# CPLD.net
KiCad netlist of a schematic drawn in Altium Designer
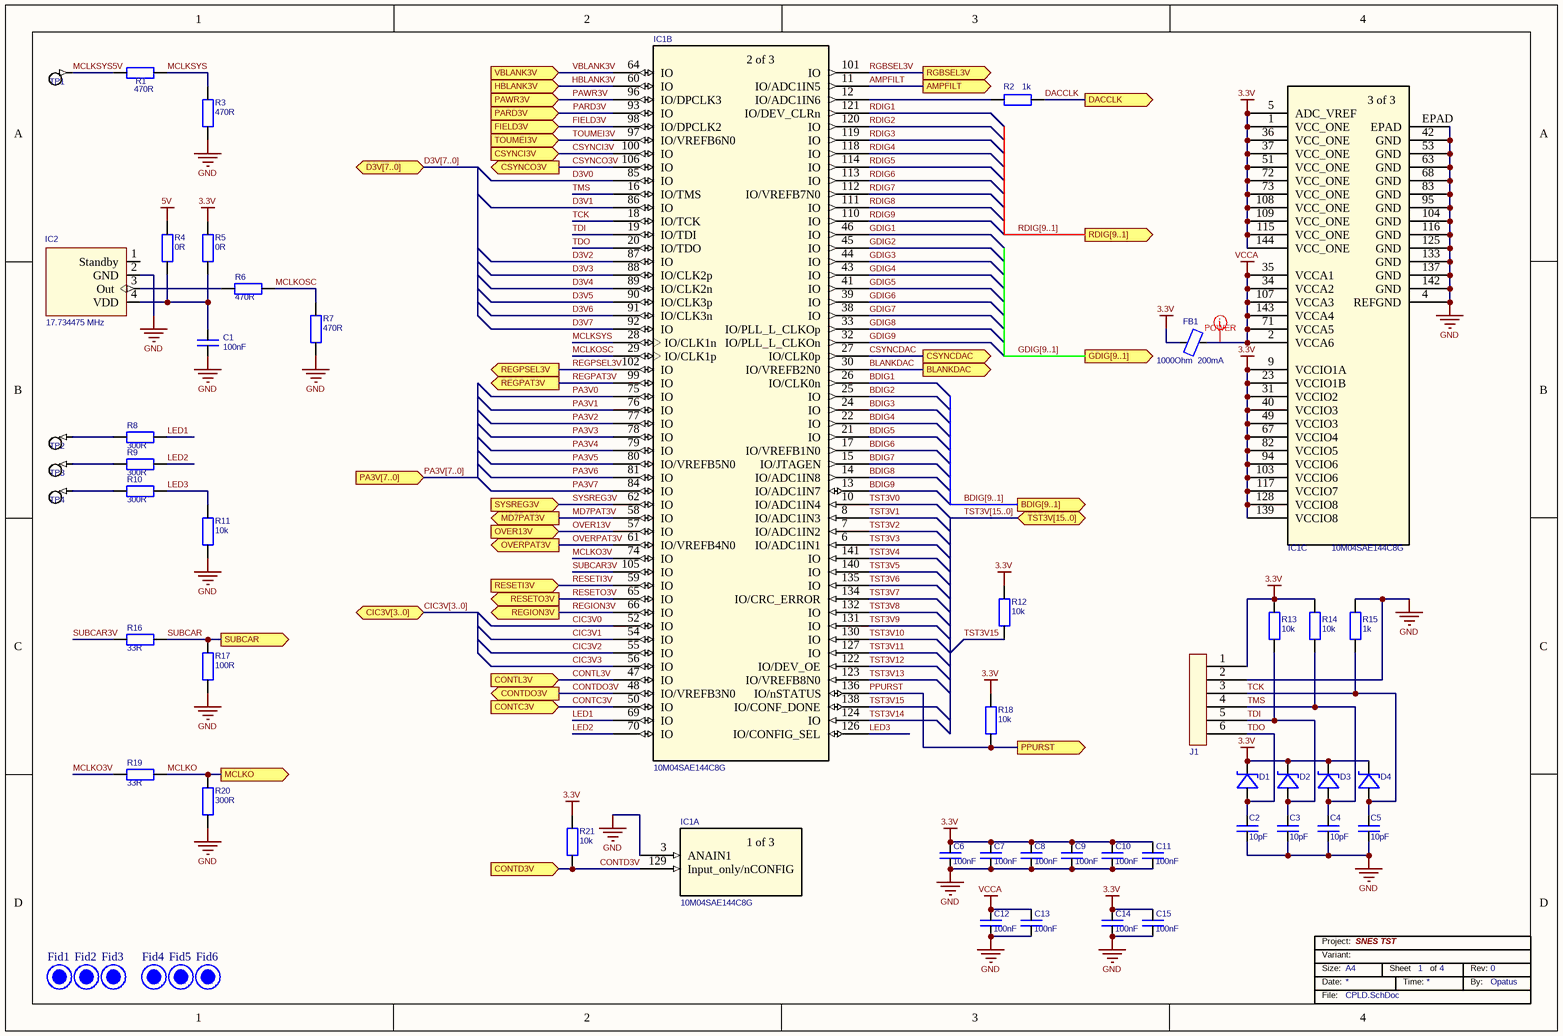
[diagram p0: CPLD.SchDoc]

(export (version "E")
  (design (tool "Eeschema 10.0.6"))
  (components
    (comp (ref "C1")
      (value "100nF")
      (footprint "Cap_0402_Chip")
      (fields
        (field (name "TOLERANCE") "±20%")
        (field (name "Comment") "Ceramic Capacitor 100nF 10V ±20% X7R 0402")
      )
      (libsource (lib "PCB") (part "Capacitor"))
    )
    (comp (ref "C2")
      (value "10pF")
      (footprint "Cap_0402_Chip")
      (fields
        (field (name "TOLERANCE") "±20%")
        (field (name "Comment") "Ceramic Capacitor 10pF 10V ±20% X7R 0402")
      )
      (libsource (lib "PCB") (part "Capacitor"))
    )
    (comp (ref "C3")
      (value "10pF")
      (footprint "Cap_0402_Chip")
      (fields
        (field (name "TOLERANCE") "±20%")
        (field (name "Comment") "Ceramic Capacitor 10pF 10V ±20% X7R 0402")
      )
      (libsource (lib "PCB") (part "Capacitor"))
    )
    (comp (ref "C4")
      (value "10pF")
      (footprint "Cap_0402_Chip")
      (fields
        (field (name "TOLERANCE") "±20%")
        (field (name "Comment") "Ceramic Capacitor 10pF 10V ±20% X7R 0402")
      )
      (libsource (lib "PCB") (part "Capacitor"))
    )
    (comp (ref "C5")
      (value "10pF")
      (footprint "Cap_0402_Chip")
      (fields
        (field (name "TOLERANCE") "±20%")
        (field (name "Comment") "Ceramic Capacitor 10pF 10V ±20% X7R 0402")
      )
      (libsource (lib "PCB") (part "Capacitor"))
    )
    (comp (ref "C6")
      (value "100nF")
      (footprint "Cap_0402_Chip")
      (fields
        (field (name "TOLERANCE") "±20%")
        (field (name "Comment") "Ceramic Capacitor 100nF 10V ±20% X7R 0402")
      )
      (libsource (lib "PCB") (part "Capacitor"))
    )
    (comp (ref "C7")
      (value "100nF")
      (footprint "Cap_0402_Chip")
      (fields
        (field (name "TOLERANCE") "±20%")
        (field (name "Comment") "Ceramic Capacitor 100nF 10V ±20% X7R 0402")
      )
      (libsource (lib "PCB") (part "Capacitor"))
    )
    (comp (ref "C8")
      (value "100nF")
      (footprint "Cap_0402_Chip")
      (fields
        (field (name "TOLERANCE") "±20%")
        (field (name "Comment") "Ceramic Capacitor 100nF 10V ±20% X7R 0402")
      )
      (libsource (lib "PCB") (part "Capacitor"))
    )
    (comp (ref "C9")
      (value "100nF")
      (footprint "Cap_0402_Chip")
      (fields
        (field (name "TOLERANCE") "±20%")
        (field (name "Comment") "Ceramic Capacitor 100nF 10V ±20% X7R 0402")
      )
      (libsource (lib "PCB") (part "Capacitor"))
    )
    (comp (ref "C10")
      (value "100nF")
      (footprint "Cap_0402_Chip")
      (fields
        (field (name "TOLERANCE") "±20%")
        (field (name "Comment") "Ceramic Capacitor 100nF 10V ±20% X7R 0402")
      )
      (libsource (lib "PCB") (part "Capacitor"))
    )
    (comp (ref "C11")
      (value "100nF")
      (footprint "Cap_0402_Chip")
      (fields
        (field (name "TOLERANCE") "±20%")
        (field (name "Comment") "Ceramic Capacitor 100nF 10V ±20% X7R 0402")
      )
      (libsource (lib "PCB") (part "Capacitor"))
    )
    (comp (ref "C12")
      (value "100nF")
      (footprint "Cap_0402_Chip")
      (fields
        (field (name "TOLERANCE") "±20%")
        (field (name "Comment") "Ceramic Capacitor 100nF 10V ±20% X7R 0402")
      )
      (libsource (lib "PCB") (part "Capacitor"))
    )
    (comp (ref "C13")
      (value "100nF")
      (footprint "Cap_0402_Chip")
      (fields
        (field (name "TOLERANCE") "±20%")
        (field (name "Comment") "Ceramic Capacitor 100nF 10V ±20% X7R 0402")
      )
      (libsource (lib "PCB") (part "Capacitor"))
    )
    (comp (ref "C14")
      (value "100nF")
      (footprint "Cap_0402_Chip")
      (fields
        (field (name "TOLERANCE") "±20%")
        (field (name "Comment") "Ceramic Capacitor 100nF 10V ±20% X7R 0402")
      )
      (libsource (lib "PCB") (part "Capacitor"))
    )
    (comp (ref "C15")
      (value "100nF")
      (footprint "Cap_0402_Chip")
      (fields
        (field (name "TOLERANCE") "±20%")
        (field (name "Comment") "Ceramic Capacitor 100nF 10V ±20% X7R 0402")
      )
      (libsource (lib "PCB") (part "Capacitor"))
    )
    (comp (ref "D1")
      (value "BAT54WS")
      (footprint "SOD323")
      (description "Schottky Diode")
      (fields (field (name "MANUFACTURER_PART_NUMBER") "BAT54WS-7-F"))
      (libsource (lib "PCB") (part "Schottky Diode"))
    )
    (comp (ref "D2")
      (value "BAT54WS")
      (footprint "SOD323")
      (description "Schottky Diode")
      (fields (field (name "MANUFACTURER_PART_NUMBER") "BAT54WS-7-F"))
      (libsource (lib "PCB") (part "Schottky Diode"))
    )
    (comp (ref "D3")
      (value "BAT54WS")
      (footprint "SOD323")
      (description "Schottky Diode")
      (fields (field (name "MANUFACTURER_PART_NUMBER") "BAT54WS-7-F"))
      (libsource (lib "PCB") (part "Schottky Diode"))
    )
    (comp (ref "D4")
      (value "BAT54WS")
      (footprint "SOD323")
      (description "Schottky Diode")
      (fields (field (name "MANUFACTURER_PART_NUMBER") "BAT54WS-7-F"))
      (libsource (lib "PCB") (part "Schottky Diode"))
    )
    (comp (ref "FB1")
      (value "1000Ohm  200mA")
      (footprint "Ind_0402_Chip")
      (fields (field (name "MANUFACTURER_PART_NUMBER") "MMZ1005S102CT000"))
      (libsource (lib "PCB") (part "Ferrite Bead"))
    )
    (comp (ref "Fid1")
      (value "Fiducial")
      (footprint "Fiducial_1_side")
      (libsource (lib "PCB") (part "Fiducial"))
    )
    (comp (ref "Fid2")
      (value "Fiducial")
      (footprint "Fiducial_1_side")
      (libsource (lib "PCB") (part "Fiducial"))
    )
    (comp (ref "Fid3")
      (value "Fiducial")
      (footprint "Fiducial_1_side")
      (libsource (lib "PCB") (part "Fiducial"))
    )
    (comp (ref "Fid4")
      (value "Fiducial")
      (footprint "Fiducial_1_side")
      (libsource (lib "PCB") (part "Fiducial"))
    )
    (comp (ref "Fid5")
      (value "Fiducial")
      (footprint "Fiducial_1_side")
      (libsource (lib "PCB") (part "Fiducial"))
    )
    (comp (ref "Fid6")
      (value "Fiducial")
      (footprint "Fiducial_1_side")
      (libsource (lib "PCB") (part "Fiducial"))
    )
    (comp (ref "IC1")
      (value "10M04SAE144C8G")
      (footprint "EQFP-144_A:1P65_")
      (description "No Description Available")
      (fields (field (name "COPYRIGHT") "Copyright (C) 2018 Accelerated Designs. All rights reserved"))
      (libsource (lib "") (part "10M08SAE144C8G_1"))
    )
    (comp (ref "IC2")
      (value "17.734475 MHz")
      (footprint "Quarz 7.5mm")
      (description "Oscillator")
      (fields
        (field (name "FREQUENCY") "17.734475 MHz")
        (field (name "MANUFACTURER_PART_NUMBER") "LFSPXO020648Bulk")
      )
      (libsource (lib "PCB") (part "Oscillator"))
    )
    (comp (ref "J1")
      (value "Conn 6P")
      (footprint "Con6P")
      (description "6 Pole Connector")
      (libsource (lib "PCB") (part "Conn 6P"))
    )
    (comp (ref "R1")
      (value "470R")
      (footprint "Res_0603_Chip")
      (fields (field (name "TOLERANCE") "±1%") (field (name "Comment") "Resistor 470R 0603 ±1%"))
      (libsource (lib "") (part "R_1"))
    )
    (comp (ref "R2")
      (value "1k")
      (footprint "Res_0402_Chip")
      (fields (field (name "TOLERANCE") "±1%") (field (name "Comment") "Resistor 1k 0402 ±1%"))
      (libsource (lib "") (part "R_2"))
    )
    (comp (ref "R3")
      (value "470R")
      (footprint "Res_0603_Chip")
      (fields (field (name "TOLERANCE") "±1%") (field (name "Comment") "Resistor 470R 0603 ±1%"))
      (libsource (lib "PCB") (part "R"))
    )
    (comp (ref "R4")
      (value "0R")
      (footprint "Res_0402_Chip")
      (fields (field (name "Comment") "Resistor 0R 0402 "))
      (libsource (lib "PCB") (part "R"))
    )
    (comp (ref "R5")
      (value "0R")
      (footprint "Res_0402_Chip")
      (fields (field (name "Comment") "Resistor 0R 0402 "))
      (libsource (lib "PCB") (part "R"))
    )
    (comp (ref "R6")
      (value "470R")
      (footprint "Res_0603_Chip")
      (fields (field (name "TOLERANCE") "±1%") (field (name "Comment") "Resistor 470R 0603 ±1%"))
      (libsource (lib "") (part "R_1"))
    )
    (comp (ref "R7")
      (value "470R")
      (footprint "Res_0603_Chip")
      (fields (field (name "TOLERANCE") "±1%") (field (name "Comment") "Resistor 470R 0603 ±1%"))
      (libsource (lib "PCB") (part "R"))
    )
    (comp (ref "R8")
      (value "300R")
      (footprint "Res_0603_Chip")
      (fields (field (name "TOLERANCE") "±1%") (field (name "Comment") "Resistor 300R 0603 ±1%"))
      (libsource (lib "") (part "R_2"))
    )
    (comp (ref "R9")
      (value "300R")
      (footprint "Res_0603_Chip")
      (fields (field (name "TOLERANCE") "±1%") (field (name "Comment") "Resistor 300R 0603 ±1%"))
      (libsource (lib "") (part "R_2"))
    )
    (comp (ref "R10")
      (value "300R")
      (footprint "Res_0603_Chip")
      (fields (field (name "TOLERANCE") "±1%") (field (name "Comment") "Resistor 300R 0603 ±1%"))
      (libsource (lib "") (part "R_2"))
    )
    (comp (ref "R11")
      (value "10k")
      (footprint "Res_0402_Chip")
      (fields (field (name "TOLERANCE") "±1%") (field (name "Comment") "Resistor 10k 0402 ±1%"))
      (libsource (lib "") (part "R_3"))
    )
    (comp (ref "R12")
      (value "10k")
      (footprint "Res_0402_Chip")
      (fields (field (name "TOLERANCE") "±1%") (field (name "Comment") "Resistor 10k 0402 ±1%"))
      (libsource (lib "PCB") (part "R"))
    )
    (comp (ref "R13")
      (value "10k")
      (footprint "Res_0402_Chip")
      (fields (field (name "TOLERANCE") "±1%") (field (name "Comment") "Resistor 10k 0402 ±1%"))
      (libsource (lib "PCB") (part "R"))
    )
    (comp (ref "R14")
      (value "10k")
      (footprint "Res_0402_Chip")
      (fields (field (name "TOLERANCE") "±1%") (field (name "Comment") "Resistor 10k 0402 ±1%"))
      (libsource (lib "PCB") (part "R"))
    )
    (comp (ref "R15")
      (value "1k")
      (footprint "Res_0402_Chip")
      (fields (field (name "TOLERANCE") "±1%") (field (name "Comment") "Resistor 1k 0402 ±1%"))
      (libsource (lib "") (part "R_3"))
    )
    (comp (ref "R16")
      (value "33R")
      (footprint "Res_0603_Chip")
      (fields (field (name "TOLERANCE") "±1%") (field (name "Comment") "Resistor 33R 0603 ±1%"))
      (libsource (lib "") (part "R_1"))
    )
    (comp (ref "R17")
      (value "100R")
      (footprint "Res_0603_Chip")
      (fields (field (name "TOLERANCE") "±1%") (field (name "Comment") "Resistor 100R 0603 ±1%"))
      (libsource (lib "PCB") (part "R"))
    )
    (comp (ref "R18")
      (value "10k")
      (footprint "Res_0402_Chip")
      (fields (field (name "TOLERANCE") "±1%") (field (name "Comment") "Resistor 10k 0402 ±1%"))
      (libsource (lib "PCB") (part "R"))
    )
    (comp (ref "R19")
      (value "33R")
      (footprint "Res_0603_Chip")
      (fields (field (name "TOLERANCE") "±1%") (field (name "Comment") "Resistor 33R 0603 ±1%"))
      (libsource (lib "") (part "R_1"))
    )
    (comp (ref "R20")
      (value "300R")
      (footprint "Res_0603_Chip")
      (fields (field (name "TOLERANCE") "±1%") (field (name "Comment") "Resistor 300R 0603 ±1%"))
      (libsource (lib "PCB") (part "R"))
    )
    (comp (ref "R21")
      (value "10k")
      (footprint "Res_0402_Chip")
      (fields (field (name "TOLERANCE") "±1%") (field (name "Comment") "Resistor 10k 0402 ±1%"))
      (libsource (lib "PCB") (part "R"))
    )
    (comp (ref "TP1")
      (value "Pin Connector")
      (footprint "Pin Connector Small")
      (libsource (lib "PCB") (part "Pin Connector"))
    )
    (comp (ref "TP2")
      (value "Pin Connector")
      (footprint "Pin Connector Small")
      (libsource (lib "PCB") (part "Pin Connector"))
    )
    (comp (ref "TP3")
      (value "Pin Connector")
      (footprint "Pin Connector Small")
      (libsource (lib "PCB") (part "Pin Connector"))
    )
    (comp (ref "TP4")
      (value "Pin Connector")
      (footprint "Pin Connector Small")
      (libsource (lib "PCB") (part "Pin Connector"))
    )
  )
  (nets
    (net (code "1") (name "/AMPFILT") (class "Default")
      (node (ref "IC1") (pin "11") (pinfunction "IO/ADC1IN5_11") (pintype "output"))
    )
    (net (code "2") (name "/BDIG1") (class "Default")
      (node (ref "IC1") (pin "26") (pinfunction "IO/CLK0n_26") (pintype "output"))
    )
    (net (code "3") (name "/BDIG2") (class "Default")
      (node (ref "IC1") (pin "25") (pinfunction "IO_25") (pintype "output"))
    )
    (net (code "4") (name "/BDIG3") (class "Default")
      (node (ref "IC1") (pin "24") (pinfunction "IO_24") (pintype "output"))
    )
    (net (code "5") (name "/BDIG4") (class "Default")
      (node (ref "IC1") (pin "22") (pinfunction "IO_22") (pintype "output"))
    )
    (net (code "6") (name "/BDIG5") (class "Default")
      (node (ref "IC1") (pin "21") (pinfunction "IO_21") (pintype "output"))
    )
    (net (code "7") (name "/BDIG6") (class "Default")
      (node (ref "IC1") (pin "17") (pinfunction "IO/VREFB1N0_17") (pintype "output"))
    )
    (net (code "8") (name "/BDIG7") (class "Default")
      (node (ref "IC1") (pin "15") (pinfunction "IO/JTAGEN_15") (pintype "output"))
    )
    (net (code "9") (name "/BDIG8") (class "Default")
      (node (ref "IC1") (pin "14") (pinfunction "IO/ADC1IN8_14") (pintype "output"))
    )
    (net (code "10") (name "/BDIG9") (class "Default")
      (node (ref "IC1") (pin "13") (pinfunction "IO/ADC1IN7_13") (pintype "bidirectional"))
    )
    (net (code "12") (name "/BLANKDAC") (class "Default")
      (node (ref "IC1") (pin "30") (pinfunction "IO/VREFB2N0_30") (pintype "output"))
    )
    (net (code "13") (name "/CIC3V0") (class "Default")
      (node (ref "IC1") (pin "52") (pinfunction "IO_52") (pintype "bidirectional"))
    )
    (net (code "14") (name "/CIC3V1") (class "Default")
      (node (ref "IC1") (pin "54") (pinfunction "IO_54") (pintype "bidirectional"))
    )
    (net (code "15") (name "/CIC3V2") (class "Default")
      (node (ref "IC1") (pin "55") (pinfunction "IO_55") (pintype "bidirectional"))
    )
    (net (code "16") (name "/CIC3V3") (class "Default")
      (node (ref "IC1") (pin "56") (pinfunction "IO_56") (pintype "bidirectional"))
    )
    (net (code "18") (name "/CONTC3V") (class "Default")
      (node (ref "IC1") (pin "50") (pinfunction "IO_50") (pintype "bidirectional"))
    )
    (net (code "19") (name "/CONTD3V") (class "Default")
      (node (ref "IC1") (pin "129") (pinfunction "Input_only/nCONFIG_129") (pintype "input"))
      (node (ref "R21") (pin "2") (pintype "passive"))
    )
    (net (code "20") (name "/CONTDO3V") (class "Default")
      (node (ref "IC1") (pin "48") (pinfunction "IO/VREFB3N0_48") (pintype "bidirectional"))
    )
    (net (code "21") (name "/CONTL3V") (class "Default")
      (node (ref "IC1") (pin "47") (pinfunction "IO_47") (pintype "bidirectional"))
    )
    (net (code "22") (name "/CSYNCDAC") (class "Default")
      (node (ref "IC1") (pin "27") (pinfunction "IO/CLK0p_27") (pintype "output"))
    )
    (net (code "23") (name "/CSYNCI3V") (class "Default")
      (node (ref "IC1") (pin "100") (pinfunction "IO_100") (pintype "bidirectional"))
    )
    (net (code "24") (name "/CSYNCO3V") (class "Default")
      (node (ref "IC1") (pin "106") (pinfunction "IO_106") (pintype "bidirectional"))
    )
    (net (code "25") (name "/D3V0") (class "Default")
      (node (ref "IC1") (pin "85") (pinfunction "IO_85") (pintype "bidirectional"))
    )
    (net (code "26") (name "/D3V1") (class "Default")
      (node (ref "IC1") (pin "86") (pinfunction "IO_86") (pintype "bidirectional"))
    )
    (net (code "27") (name "/D3V2") (class "Default")
      (node (ref "IC1") (pin "87") (pinfunction "IO_87") (pintype "bidirectional"))
    )
    (net (code "28") (name "/D3V3") (class "Default")
      (node (ref "IC1") (pin "88") (pinfunction "IO/CLK2p_88") (pintype "bidirectional"))
    )
    (net (code "29") (name "/D3V4") (class "Default")
      (node (ref "IC1") (pin "89") (pinfunction "IO/CLK2n_89") (pintype "bidirectional"))
    )
    (net (code "30") (name "/D3V5") (class "Default")
      (node (ref "IC1") (pin "90") (pinfunction "IO/CLK3p_90") (pintype "bidirectional"))
    )
    (net (code "31") (name "/D3V6") (class "Default")
      (node (ref "IC1") (pin "91") (pinfunction "IO/CLK3n_91") (pintype "bidirectional"))
    )
    (net (code "32") (name "/D3V7") (class "Default")
      (node (ref "IC1") (pin "92") (pinfunction "IO_92") (pintype "bidirectional"))
    )
    (net (code "34") (name "/DACCLK") (class "Default") (node (ref "R2") (pin "2") (pintype "passive")))
    (net (code "35") (name "/FIELD3V") (class "Default")
      (node (ref "IC1") (pin "98") (pinfunction "IO/DPCLK2_98") (pintype "bidirectional"))
    )
    (net (code "36") (name "/GDIG1") (class "Default")
      (node (ref "IC1") (pin "46") (pinfunction "IO_46") (pintype "output"))
    )
    (net (code "37") (name "/GDIG2") (class "Default")
      (node (ref "IC1") (pin "45") (pinfunction "IO_45") (pintype "output"))
    )
    (net (code "38") (name "/GDIG3") (class "Default")
      (node (ref "IC1") (pin "44") (pinfunction "IO_44") (pintype "output"))
    )
    (net (code "39") (name "/GDIG4") (class "Default")
      (node (ref "IC1") (pin "43") (pinfunction "IO_43") (pintype "output"))
    )
    (net (code "40") (name "/GDIG5") (class "Default")
      (node (ref "IC1") (pin "41") (pinfunction "IO_41") (pintype "output"))
    )
    (net (code "41") (name "/GDIG6") (class "Default")
      (node (ref "IC1") (pin "39") (pinfunction "IO_39") (pintype "output"))
    )
    (net (code "42") (name "/GDIG7") (class "Default")
      (node (ref "IC1") (pin "38") (pinfunction "IO_38") (pintype "output"))
    )
    (net (code "43") (name "/GDIG8") (class "Default")
      (node (ref "IC1") (pin "33") (pinfunction "IO/PLL_L_CLKOp_33") (pintype "output"))
    )
    (net (code "44") (name "/GDIG9") (class "Default")
      (node (ref "IC1") (pin "32") (pinfunction "IO/PLL_L_CLKOn_32") (pintype "output"))
    )
    (net (code "46") (name "/HBLANK3V") (class "Default")
      (node (ref "IC1") (pin "60") (pinfunction "IO_60") (pintype "bidirectional"))
    )
    (net (code "47") (name "/LED1") (class "Default")
      (node (ref "IC1") (pin "69") (pinfunction "IO_69") (pintype "bidirectional"))
      (node (ref "R8") (pin "2") (pintype "passive"))
    )
    (net (code "48") (name "/LED2") (class "Default")
      (node (ref "IC1") (pin "70") (pinfunction "IO_70") (pintype "bidirectional"))
      (node (ref "R9") (pin "2") (pintype "passive"))
    )
    (net (code "49") (name "/LED3") (class "Default")
      (node (ref "IC1") (pin "126") (pinfunction "IO/CONFIG_SEL_126") (pintype "bidirectional"))
      (node (ref "R10") (pin "2") (pintype "passive"))
      (node (ref "R11") (pin "2") (pintype "passive"))
    )
    (net (code "50") (name "/MCLKO") (class "Default")
      (node (ref "R19") (pin "1") (pintype "passive"))
      (node (ref "R20") (pin "1") (pintype "passive"))
    )
    (net (code "51") (name "/MCLKO3V") (class "Default")
      (node (ref "IC1") (pin "74") (pinfunction "IO_74") (pintype "bidirectional"))
      (node (ref "R19") (pin "2") (pintype "passive"))
    )
    (net (code "52") (name "/MCLKOSC") (class "Default")
      (node (ref "IC1") (pin "29") (pinfunction "IO/CLK1p_29") (pintype "bidirectional"))
      (node (ref "R6") (pin "1") (pintype "passive"))
      (node (ref "R7") (pin "1") (pintype "passive"))
    )
    (net (code "53") (name "/MCLKSYS") (class "Default")
      (node (ref "IC1") (pin "28") (pinfunction "IO/CLK1n_28") (pintype "bidirectional"))
      (node (ref "R1") (pin "1") (pintype "passive"))
      (node (ref "R3") (pin "1") (pintype "passive"))
    )
    (net (code "54") (name "/MCLKSYS5V") (class "Default")
      (node (ref "R1") (pin "2") (pintype "passive"))
      (node (ref "TP1") (pin "1") (pinfunction "0_1") (pintype "input"))
    )
    (net (code "55") (name "/MD7PAT3V") (class "Default")
      (node (ref "IC1") (pin "58") (pinfunction "IO_58") (pintype "bidirectional"))
    )
    (net (code "56") (name "/OVER13V") (class "Default")
      (node (ref "IC1") (pin "57") (pinfunction "IO_57") (pintype "bidirectional"))
    )
    (net (code "57") (name "/OVERPAT3V") (class "Default")
      (node (ref "IC1") (pin "61") (pinfunction "IO/VREFB4N0_61") (pintype "bidirectional"))
    )
    (net (code "58") (name "/PA3V0") (class "Default")
      (node (ref "IC1") (pin "75") (pinfunction "IO_75") (pintype "bidirectional"))
    )
    (net (code "59") (name "/PA3V1") (class "Default")
      (node (ref "IC1") (pin "76") (pinfunction "IO_76") (pintype "bidirectional"))
    )
    (net (code "60") (name "/PA3V2") (class "Default")
      (node (ref "IC1") (pin "77") (pinfunction "IO_77") (pintype "bidirectional"))
    )
    (net (code "61") (name "/PA3V3") (class "Default")
      (node (ref "IC1") (pin "78") (pinfunction "IO_78") (pintype "bidirectional"))
    )
    (net (code "62") (name "/PA3V4") (class "Default")
      (node (ref "IC1") (pin "79") (pinfunction "IO_79") (pintype "bidirectional"))
    )
    (net (code "63") (name "/PA3V5") (class "Default")
      (node (ref "IC1") (pin "80") (pinfunction "IO/VREFB5N0_80") (pintype "bidirectional"))
    )
    (net (code "64") (name "/PA3V6") (class "Default")
      (node (ref "IC1") (pin "81") (pinfunction "IO_81") (pintype "bidirectional"))
    )
    (net (code "65") (name "/PA3V7") (class "Default")
      (node (ref "IC1") (pin "84") (pinfunction "IO_84") (pintype "bidirectional"))
    )
    (net (code "67") (name "/PARD3V") (class "Default")
      (node (ref "IC1") (pin "93") (pinfunction "IO_93") (pintype "bidirectional"))
    )
    (net (code "68") (name "/PAWR3V") (class "Default")
      (node (ref "IC1") (pin "96") (pinfunction "IO/DPCLK3_96") (pintype "bidirectional"))
    )
    (net (code "69") (name "/PPURST") (class "Default")
      (node (ref "IC1") (pin "136") (pinfunction "IO/nSTATUS_136") (pintype "bidirectional"))
      (node (ref "R18") (pin "2") (pintype "passive"))
    )
    (net (code "70") (name "/RDIG1") (class "Default")
      (node (ref "IC1") (pin "121") (pinfunction "IO/DEV_CLRn_121") (pintype "output"))
    )
    (net (code "71") (name "/RDIG2") (class "Default")
      (node (ref "IC1") (pin "120") (pinfunction "IO_120") (pintype "output"))
    )
    (net (code "72") (name "/RDIG3") (class "Default")
      (node (ref "IC1") (pin "119") (pinfunction "IO_119") (pintype "output"))
    )
    (net (code "73") (name "/RDIG4") (class "Default")
      (node (ref "IC1") (pin "118") (pinfunction "IO_118") (pintype "output"))
    )
    (net (code "74") (name "/RDIG5") (class "Default")
      (node (ref "IC1") (pin "114") (pinfunction "IO_114") (pintype "output"))
    )
    (net (code "75") (name "/RDIG6") (class "Default")
      (node (ref "IC1") (pin "113") (pinfunction "IO_113") (pintype "output"))
    )
    (net (code "76") (name "/RDIG7") (class "Default")
      (node (ref "IC1") (pin "112") (pinfunction "IO/VREFB7N0_112") (pintype "output"))
    )
    (net (code "77") (name "/RDIG8") (class "Default")
      (node (ref "IC1") (pin "111") (pinfunction "IO_111") (pintype "output"))
    )
    (net (code "78") (name "/RDIG9") (class "Default")
      (node (ref "IC1") (pin "110") (pinfunction "IO_110") (pintype "output"))
    )
    (net (code "80") (name "/REGION3V") (class "Default")
      (node (ref "IC1") (pin "66") (pinfunction "IO_66") (pintype "bidirectional"))
    )
    (net (code "81") (name "/REGPAT3V") (class "Default")
      (node (ref "IC1") (pin "99") (pinfunction "IO_99") (pintype "bidirectional"))
    )
    (net (code "82") (name "/REGPSEL3V") (class "Default")
      (node (ref "IC1") (pin "102") (pinfunction "IO_102") (pintype "bidirectional"))
    )
    (net (code "83") (name "/RESETI3V") (class "Default")
      (node (ref "IC1") (pin "59") (pinfunction "IO_59") (pintype "bidirectional"))
    )
    (net (code "84") (name "/RESETO3V") (class "Default")
      (node (ref "IC1") (pin "65") (pinfunction "IO_65") (pintype "bidirectional"))
    )
    (net (code "85") (name "/RGBSEL3V") (class "Default")
      (node (ref "IC1") (pin "101") (pinfunction "IO_101") (pintype "output"))
    )
    (net (code "86") (name "/SUBCAR") (class "Default")
      (node (ref "R16") (pin "1") (pintype "passive"))
      (node (ref "R17") (pin "1") (pintype "passive"))
    )
    (net (code "87") (name "/SUBCAR3V") (class "Default")
      (node (ref "IC1") (pin "105") (pinfunction "IO_105") (pintype "bidirectional"))
      (node (ref "R16") (pin "2") (pintype "passive"))
    )
    (net (code "88") (name "/SYSREG3V") (class "Default")
      (node (ref "IC1") (pin "62") (pinfunction "IO_62") (pintype "bidirectional"))
    )
    (net (code "89") (name "/TCK") (class "Default")
      (node (ref "C5") (pin "1") (pintype "passive"))
      (node (ref "D4") (pin "2") (pinfunction "A_2") (pintype "passive"))
      (node (ref "IC1") (pin "18") (pinfunction "IO/TCK_18") (pintype "bidirectional"))
      (node (ref "J1") (pin "3") (pintype "passive"))
      (node (ref "R15") (pin "1") (pintype "passive"))
    )
    (net (code "90") (name "/TDI") (class "Default")
      (node (ref "C3") (pin "1") (pintype "passive"))
      (node (ref "D2") (pin "2") (pinfunction "A_2") (pintype "passive"))
      (node (ref "IC1") (pin "19") (pinfunction "IO/TDI_19") (pintype "bidirectional"))
      (node (ref "J1") (pin "5") (pintype "passive"))
      (node (ref "R13") (pin "2") (pintype "passive"))
    )
    (net (code "91") (name "/TDO") (class "Default")
      (node (ref "C2") (pin "1") (pintype "passive"))
      (node (ref "D1") (pin "2") (pinfunction "A_2") (pintype "passive"))
      (node (ref "IC1") (pin "20") (pinfunction "IO/TDO_20") (pintype "bidirectional"))
      (node (ref "J1") (pin "6") (pintype "passive"))
    )
    (net (code "92") (name "/TMS") (class "Default")
      (node (ref "C4") (pin "1") (pintype "passive"))
      (node (ref "D3") (pin "2") (pinfunction "A_2") (pintype "passive"))
      (node (ref "IC1") (pin "16") (pinfunction "IO/TMS_16") (pintype "bidirectional"))
      (node (ref "J1") (pin "4") (pintype "passive"))
      (node (ref "R14") (pin "2") (pintype "passive"))
    )
    (net (code "93") (name "/TOUMEI3V") (class "Default")
      (node (ref "IC1") (pin "97") (pinfunction "IO/VREFB6N0_97") (pintype "bidirectional"))
    )
    (net (code "94") (name "/TST3V0") (class "Default")
      (node (ref "IC1") (pin "10") (pinfunction "IO/ADC1IN4_10") (pintype "input"))
    )
    (net (code "95") (name "/TST3V1") (class "Default")
      (node (ref "IC1") (pin "8") (pinfunction "IO/ADC1IN3_8") (pintype "input"))
    )
    (net (code "96") (name "/TST3V2") (class "Default")
      (node (ref "IC1") (pin "7") (pinfunction "IO/ADC1IN2_7") (pintype "input"))
    )
    (net (code "97") (name "/TST3V3") (class "Default")
      (node (ref "IC1") (pin "6") (pinfunction "IO/ADC1IN1_6") (pintype "input"))
    )
    (net (code "98") (name "/TST3V4") (class "Default")
      (node (ref "IC1") (pin "141") (pinfunction "IO_141") (pintype "input"))
    )
    (net (code "99") (name "/TST3V5") (class "Default")
      (node (ref "IC1") (pin "140") (pinfunction "IO_140") (pintype "input"))
    )
    (net (code "100") (name "/TST3V6") (class "Default")
      (node (ref "IC1") (pin "135") (pinfunction "IO_135") (pintype "input"))
    )
    (net (code "101") (name "/TST3V7") (class "Default")
      (node (ref "IC1") (pin "134") (pinfunction "IO/CRC_ERROR_134") (pintype "input"))
    )
    (net (code "102") (name "/TST3V8") (class "Default")
      (node (ref "IC1") (pin "132") (pinfunction "IO_132") (pintype "input"))
    )
    (net (code "103") (name "/TST3V9") (class "Default")
      (node (ref "IC1") (pin "131") (pinfunction "IO_131") (pintype "input"))
    )
    (net (code "104") (name "/TST3V10") (class "Default")
      (node (ref "IC1") (pin "130") (pinfunction "IO_130") (pintype "input"))
    )
    (net (code "105") (name "/TST3V11") (class "Default")
      (node (ref "IC1") (pin "127") (pinfunction "IO_127") (pintype "input"))
    )
    (net (code "106") (name "/TST3V12") (class "Default")
      (node (ref "IC1") (pin "122") (pinfunction "IO/DEV_OE_122") (pintype "input"))
    )
    (net (code "107") (name "/TST3V13") (class "Default")
      (node (ref "IC1") (pin "123") (pinfunction "IO/VREFB8N0_123") (pintype "input"))
    )
    (net (code "108") (name "/TST3V14") (class "Default")
      (node (ref "IC1") (pin "124") (pinfunction "IO_124") (pintype "input"))
    )
    (net (code "109") (name "/TST3V15") (class "Default")
      (node (ref "IC1") (pin "138") (pinfunction "IO/CONF_DONE_138") (pintype "bidirectional"))
      (node (ref "R12") (pin "2") (pintype "passive"))
    )
    (net (code "111") (name "/VBLANK3V") (class "Default")
      (node (ref "IC1") (pin "64") (pinfunction "IO_64") (pintype "bidirectional"))
    )
    (net (code "112") (name "3.3V") (class "Default")
      (node (ref "C10") (pin "1") (pintype "passive"))
      (node (ref "C11") (pin "1") (pintype "passive"))
      (node (ref "C14") (pin "1") (pintype "passive"))
      (node (ref "C15") (pin "1") (pintype "passive"))
      (node (ref "C6") (pin "1") (pintype "passive"))
      (node (ref "C7") (pin "1") (pintype "passive"))
      (node (ref "C8") (pin "1") (pintype "passive"))
      (node (ref "C9") (pin "1") (pintype "passive"))
      (node (ref "D1") (pin "1") (pinfunction "K_1") (pintype "passive"))
      (node (ref "D2") (pin "1") (pinfunction "K_1") (pintype "passive"))
      (node (ref "D3") (pin "1") (pinfunction "K_1") (pintype "passive"))
      (node (ref "D4") (pin "1") (pinfunction "K_1") (pintype "passive"))
      (node (ref "FB1") (pin "1") (pintype "passive"))
      (node (ref "IC1") (pin "1") (pinfunction "VCC_ONE_1") (pintype "power_in"))
      (node (ref "IC1") (pin "103") (pinfunction "VCCIO6_103") (pintype "power_in"))
      (node (ref "IC1") (pin "108") (pinfunction "VCC_ONE_108") (pintype "power_in"))
      (node (ref "IC1") (pin "109") (pinfunction "VCC_ONE_109") (pintype "power_in"))
      (node (ref "IC1") (pin "115") (pinfunction "VCC_ONE_115") (pintype "power_in"))
      (node (ref "IC1") (pin "117") (pinfunction "VCCIO7_117") (pintype "power_in"))
      (node (ref "IC1") (pin "128") (pinfunction "VCCIO8_128") (pintype "power_in"))
      (node (ref "IC1") (pin "139") (pinfunction "VCCIO8_139") (pintype "power_in"))
      (node (ref "IC1") (pin "144") (pinfunction "VCC_ONE_144") (pintype "power_in"))
      (node (ref "IC1") (pin "23") (pinfunction "VCCIO1B_23") (pintype "power_in"))
      (node (ref "IC1") (pin "31") (pinfunction "VCCIO2_31") (pintype "power_in"))
      (node (ref "IC1") (pin "36") (pinfunction "VCC_ONE_36") (pintype "power_in"))
      (node (ref "IC1") (pin "37") (pinfunction "VCC_ONE_37") (pintype "power_in"))
      (node (ref "IC1") (pin "40") (pinfunction "VCCIO3_40") (pintype "power_in"))
      (node (ref "IC1") (pin "49") (pinfunction "VCCIO3_49") (pintype "power_in"))
      (node (ref "IC1") (pin "5") (pinfunction "ADC_VREF_5") (pintype "power_in"))
      (node (ref "IC1") (pin "51") (pinfunction "VCC_ONE_51") (pintype "power_in"))
      (node (ref "IC1") (pin "67") (pinfunction "VCCIO4_67") (pintype "power_in"))
      (node (ref "IC1") (pin "72") (pinfunction "VCC_ONE_72") (pintype "power_in"))
      (node (ref "IC1") (pin "73") (pinfunction "VCC_ONE_73") (pintype "power_in"))
      (node (ref "IC1") (pin "82") (pinfunction "VCCIO5_82") (pintype "power_in"))
      (node (ref "IC1") (pin "9") (pinfunction "VCCIO1A_9") (pintype "power_in"))
      (node (ref "IC1") (pin "94") (pinfunction "VCCIO6_94") (pintype "power_in"))
      (node (ref "J1") (pin "1") (pintype "passive"))
      (node (ref "R12") (pin "1") (pintype "passive"))
      (node (ref "R13") (pin "1") (pintype "passive"))
      (node (ref "R14") (pin "1") (pintype "passive"))
      (node (ref "R18") (pin "1") (pintype "passive"))
      (node (ref "R21") (pin "1") (pintype "passive"))
      (node (ref "R5") (pin "1") (pintype "passive"))
    )
    (net (code "113") (name "5V") (class "Default") (node (ref "R4") (pin "1") (pintype "passive")))
    (net (code "114") (name "GND") (class "Default")
      (node (ref "C1") (pin "2") (pintype "passive"))
      (node (ref "C10") (pin "2") (pintype "passive"))
      (node (ref "C11") (pin "2") (pintype "passive"))
      (node (ref "C12") (pin "2") (pintype "passive"))
      (node (ref "C13") (pin "2") (pintype "passive"))
      (node (ref "C14") (pin "2") (pintype "passive"))
      (node (ref "C15") (pin "2") (pintype "passive"))
      (node (ref "C2") (pin "2") (pintype "passive"))
      (node (ref "C3") (pin "2") (pintype "passive"))
      (node (ref "C4") (pin "2") (pintype "passive"))
      (node (ref "C5") (pin "2") (pintype "passive"))
      (node (ref "C6") (pin "2") (pintype "passive"))
      (node (ref "C7") (pin "2") (pintype "passive"))
      (node (ref "C8") (pin "2") (pintype "passive"))
      (node (ref "C9") (pin "2") (pintype "passive"))
      (node (ref "IC1") (pin "104") (pinfunction "GND_104") (pintype "power_in"))
      (node (ref "IC1") (pin "116") (pinfunction "GND_116") (pintype "power_in"))
      (node (ref "IC1") (pin "125") (pinfunction "GND_125") (pintype "power_in"))
      (node (ref "IC1") (pin "133") (pinfunction "GND_133") (pintype "power_in"))
      (node (ref "IC1") (pin "137") (pinfunction "GND_137") (pintype "power_in"))
      (node (ref "IC1") (pin "142") (pinfunction "GND_142") (pintype "power_in"))
      (node (ref "IC1") (pin "3") (pinfunction "ANAIN1_3") (pintype "input"))
      (node (ref "IC1") (pin "4") (pinfunction "REFGND_4") (pintype "power_in"))
      (node (ref "IC1") (pin "42") (pinfunction "GND_42") (pintype "power_in"))
      (node (ref "IC1") (pin "53") (pinfunction "GND_53") (pintype "power_in"))
      (node (ref "IC1") (pin "63") (pinfunction "GND_63") (pintype "power_in"))
      (node (ref "IC1") (pin "68") (pinfunction "GND_68") (pintype "power_in"))
      (node (ref "IC1") (pin "83") (pinfunction "GND_83") (pintype "power_in"))
      (node (ref "IC1") (pin "95") (pinfunction "GND_95") (pintype "power_in"))
      (node (ref "IC1") (pin "EPAD") (pinfunction "EPAD_EPAD") (pintype "power_in"))
      (node (ref "IC2") (pin "2") (pinfunction "GND_2") (pintype "power_in"))
      (node (ref "J1") (pin "2") (pintype "passive"))
      (node (ref "R11") (pin "1") (pintype "passive"))
      (node (ref "R15") (pin "2") (pintype "passive"))
      (node (ref "R17") (pin "2") (pintype "passive"))
      (node (ref "R20") (pin "2") (pintype "passive"))
      (node (ref "R3") (pin "2") (pintype "passive"))
      (node (ref "R7") (pin "2") (pintype "passive"))
    )
    (net (code "115") (name "Net-(IC1B-IO{slash}ADC1IN6)") (class "Default")
      (node (ref "IC1") (pin "12") (pinfunction "IO/ADC1IN6_12") (pintype "output"))
      (node (ref "R2") (pin "1") (pintype "passive"))
    )
    (net (code "116") (name "Net-(IC2-Out)") (class "Default")
      (node (ref "IC2") (pin "3") (pinfunction "Out_3") (pintype "output"))
      (node (ref "R6") (pin "2") (pintype "passive"))
    )
    (net (code "117") (name "Net-(IC2-VDD)") (class "Default")
      (node (ref "C1") (pin "1") (pintype "passive"))
      (node (ref "IC2") (pin "4") (pinfunction "VDD_4") (pintype "power_in"))
      (node (ref "R4") (pin "2") (pintype "passive"))
      (node (ref "R5") (pin "2") (pintype "passive"))
    )
    (net (code "118") (name "Net-(TP2-0)") (class "Default")
      (node (ref "R8") (pin "1") (pintype "passive"))
      (node (ref "TP2") (pin "1") (pinfunction "0_1") (pintype "input"))
    )
    (net (code "119") (name "Net-(TP3-0)") (class "Default")
      (node (ref "R9") (pin "1") (pintype "passive"))
      (node (ref "TP3") (pin "1") (pinfunction "0_1") (pintype "input"))
    )
    (net (code "120") (name "Net-(TP4-0)") (class "Default")
      (node (ref "R10") (pin "1") (pintype "passive"))
      (node (ref "TP4") (pin "1") (pinfunction "0_1") (pintype "input"))
    )
    (net (code "121") (name "VCCA") (class "Default")
      (node (ref "C12") (pin "1") (pintype "passive"))
      (node (ref "C13") (pin "1") (pintype "passive"))
      (node (ref "FB1") (pin "2") (pintype "passive"))
      (node (ref "IC1") (pin "107") (pinfunction "VCCA3_107") (pintype "power_in"))
      (node (ref "IC1") (pin "143") (pinfunction "VCCA4_143") (pintype "power_in"))
      (node (ref "IC1") (pin "2") (pinfunction "VCCA6_2") (pintype "power_in"))
      (node (ref "IC1") (pin "34") (pinfunction "VCCA2_34") (pintype "power_in"))
      (node (ref "IC1") (pin "35") (pinfunction "VCCA1_35") (pintype "power_in"))
      (node (ref "IC1") (pin "71") (pinfunction "VCCA5_71") (pintype "power_in"))
    )
    (net (code "122") (name "unconnected-(IC2-Standby-Pad1)") (class "Default")
      (node (ref "IC2") (pin "1") (pinfunction "Standby_1") (pintype "passive"))
    )
  )
)
